# ard-dht.net
KiCad netlist of a schematic drawn in EAGLE
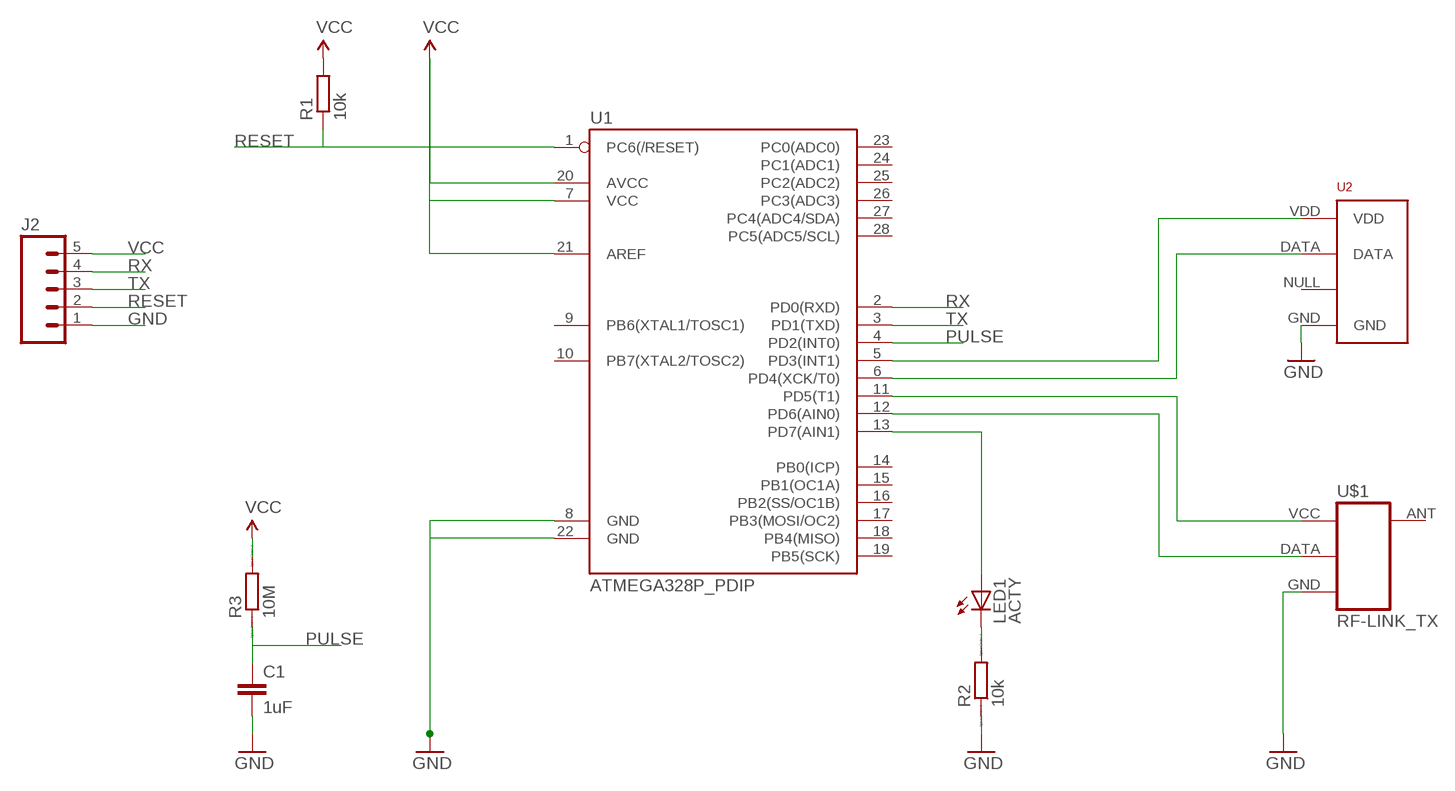
[diagram p0: schematic, sheet 1]

(export (version "E")
  (design (tool "Eeschema 10.0.6"))
  (components
    (comp (ref "C1")
      (value "1uF")
      (footprint "eagle-import:C5B5")
      (libsource (lib "eagle-import") (part "C5/5"))
    )
    (comp (ref "J2")
      (value "M05PTH_LONGPADS")
      (footprint "eagle-import:1X05_LONGPADS")
      (libsource (lib "eagle-import") (part "M05PTH_LONGPADS"))
    )
    (comp (ref "LED1")
      (value "ACTY")
      (footprint "eagle-import:LED3MM")
      (libsource (lib "eagle-import") (part "LED3MM"))
    )
    (comp (ref "R1")
      (value "10k")
      (footprint "eagle-import:0207_10")
      (libsource (lib "eagle-import") (part "R-EU_0207/10"))
    )
    (comp (ref "R2")
      (value "10k")
      (footprint "eagle-import:0204_7")
      (libsource (lib "eagle-import") (part "R0204/7"))
    )
    (comp (ref "R3")
      (value "10M")
      (footprint "eagle-import:0204_7")
      (libsource (lib "eagle-import") (part "R0204/7"))
    )
    (comp (ref "U$1")
      (value "RF-LINK_TX")
      (footprint "eagle-import:RF-LINK_TX")
      (libsource (lib "eagle-import") (part "RF-LINK_TX"))
    )
    (comp (ref "U1")
      (value "ATMEGA328P_PDIP")
      (footprint "eagle-import:DIL28-3")
      (libsource (lib "eagle-import") (part "ATMEGA328P_PDIP"))
    )
    (comp (ref "U2")
      (value "RHT03_DHT-22_AM2302")
      (footprint "eagle-import:RHT03_DHT-22")
      (libsource (lib "eagle-import") (part "RHT03_DHT-22_AM2302"))
    )
  )
  (nets
    (net (code "1") (name "/PULSE") (class "Default")
      (node (ref "C1") (pin "1") (pinfunction "1_1") (pintype "passive"))
      (node (ref "R3") (pin "1") (pinfunction "1_1") (pintype "passive"))
      (node (ref "U1") (pin "4") (pinfunction "PD2(INT0)_4") (pintype "bidirectional"))
    )
    (net (code "2") (name "/RESET") (class "Default")
      (node (ref "J2") (pin "2") (pinfunction "2_2") (pintype "passive"))
      (node (ref "R1") (pin "1") (pinfunction "1_1") (pintype "passive"))
      (node (ref "U1") (pin "1") (pinfunction "PC6(/RESET)_1") (pintype "bidirectional"))
    )
    (net (code "3") (name "/RX") (class "Default")
      (node (ref "J2") (pin "4") (pinfunction "4_4") (pintype "passive"))
      (node (ref "U1") (pin "2") (pinfunction "PD0(RXD)_2") (pintype "bidirectional"))
    )
    (net (code "4") (name "/TX") (class "Default")
      (node (ref "J2") (pin "3") (pinfunction "3_3") (pintype "passive"))
      (node (ref "U1") (pin "3") (pinfunction "PD1(TXD)_3") (pintype "bidirectional"))
    )
    (net (code "5") (name "GND") (class "Default")
      (node (ref "C1") (pin "2") (pinfunction "2_2") (pintype "passive"))
      (node (ref "J2") (pin "1") (pinfunction "1_1") (pintype "passive"))
      (node (ref "R2") (pin "1") (pinfunction "1_1") (pintype "passive"))
      (node (ref "U$1") (pin "GND") (pinfunction "GND_GND") (pintype "power_in"))
      (node (ref "U1") (pin "22") (pinfunction "GND_22") (pintype "bidirectional"))
      (node (ref "U1") (pin "8") (pinfunction "GND_8") (pintype "bidirectional"))
      (node (ref "U2") (pin "GND") (pinfunction "GND_GND") (pintype "power_in"))
    )
    (net (code "6") (name "Net-(LED1-C)") (class "Default")
      (node (ref "LED1") (pin "K") (pinfunction "C_K") (pintype "passive"))
      (node (ref "R2") (pin "2") (pinfunction "2_2") (pintype "passive"))
    )
    (net (code "7") (name "Net-(U$1-+5V)") (class "Default")
      (node (ref "U$1") (pin "VCC") (pinfunction "+5V_VCC") (pintype "power_in"))
      (node (ref "U1") (pin "11") (pinfunction "PD5(T1)_11") (pintype "bidirectional"))
    )
    (net (code "8") (name "Net-(U1-PD3(INT1))") (class "Default")
      (node (ref "U1") (pin "5") (pinfunction "PD3(INT1)_5") (pintype "bidirectional"))
      (node (ref "U2") (pin "VDD") (pinfunction "VDD_VDD") (pintype "power_in"))
    )
    (net (code "9") (name "Net-(U1-PD4(XCK{slash}T0))") (class "Default")
      (node (ref "U1") (pin "6") (pinfunction "PD4(XCK/T0)_6") (pintype "bidirectional"))
      (node (ref "U2") (pin "DATA") (pinfunction "DATA_DATA") (pintype "bidirectional"))
    )
    (net (code "10") (name "Net-(U1-PD6(AIN0))") (class "Default")
      (node (ref "U$1") (pin "DATA") (pinfunction "DATA_DATA") (pintype "input"))
      (node (ref "U1") (pin "12") (pinfunction "PD6(AIN0)_12") (pintype "bidirectional"))
    )
    (net (code "11") (name "Net-(U1-PD7(AIN1))") (class "Default")
      (node (ref "LED1") (pin "A") (pinfunction "A_A") (pintype "passive"))
      (node (ref "U1") (pin "13") (pinfunction "PD7(AIN1)_13") (pintype "bidirectional"))
    )
    (net (code "12") (name "VCC") (class "Default")
      (node (ref "J2") (pin "5") (pinfunction "5_5") (pintype "passive"))
      (node (ref "R1") (pin "2") (pinfunction "2_2") (pintype "passive"))
      (node (ref "R3") (pin "2") (pinfunction "2_2") (pintype "passive"))
      (node (ref "U1") (pin "20") (pinfunction "AVCC_20") (pintype "bidirectional"))
      (node (ref "U1") (pin "21") (pinfunction "AREF_21") (pintype "bidirectional"))
      (node (ref "U1") (pin "7") (pinfunction "VCC_7") (pintype "bidirectional"))
    )
    (net (code "13") (name "unconnected-(U$1-PadANT)") (class "Default")
      (node (ref "U$1") (pin "ANT") (pinfunction "ANT_ANT") (pintype "passive"))
    )
    (net (code "14") (name "unconnected-(U1-PB0(ICP)-Pad14)") (class "Default")
      (node (ref "U1") (pin "14") (pinfunction "PB0(ICP)_14") (pintype "bidirectional"))
    )
    (net (code "15") (name "unconnected-(U1-PB1(OC1A)-Pad15)") (class "Default")
      (node (ref "U1") (pin "15") (pinfunction "PB1(OC1A)_15") (pintype "bidirectional"))
    )
    (net (code "16") (name "unconnected-(U1-PB2(SS{slash}OC1B)-Pad16)") (class "Default")
      (node (ref "U1") (pin "16") (pinfunction "PB2(SS/OC1B)_16") (pintype "bidirectional"))
    )
    (net (code "17") (name "unconnected-(U1-PB3(MOSI{slash}OC2)-Pad17)") (class "Default")
      (node (ref "U1") (pin "17") (pinfunction "PB3(MOSI/OC2)_17") (pintype "bidirectional"))
    )
    (net (code "18") (name "unconnected-(U1-PB4(MISO)-Pad18)") (class "Default")
      (node (ref "U1") (pin "18") (pinfunction "PB4(MISO)_18") (pintype "bidirectional"))
    )
    (net (code "19") (name "unconnected-(U1-PB5(SCK)-Pad19)") (class "Default")
      (node (ref "U1") (pin "19") (pinfunction "PB5(SCK)_19") (pintype "bidirectional"))
    )
    (net (code "20") (name "unconnected-(U1-PB6(XTAL1{slash}TOSC1)-Pad9)") (class "Default")
      (node (ref "U1") (pin "9") (pinfunction "PB6(XTAL1/TOSC1)_9") (pintype "bidirectional"))
    )
    (net (code "21") (name "unconnected-(U1-PB7(XTAL2{slash}TOSC2)-Pad10)") (class "Default")
      (node (ref "U1") (pin "10") (pinfunction "PB7(XTAL2/TOSC2)_10") (pintype "bidirectional"))
    )
    (net (code "22") (name "unconnected-(U1-PC0(ADC0)-Pad23)") (class "Default")
      (node (ref "U1") (pin "23") (pinfunction "PC0(ADC0)_23") (pintype "bidirectional"))
    )
    (net (code "23") (name "unconnected-(U1-PC1(ADC1)-Pad24)") (class "Default")
      (node (ref "U1") (pin "24") (pinfunction "PC1(ADC1)_24") (pintype "bidirectional"))
    )
    (net (code "24") (name "unconnected-(U1-PC2(ADC2)-Pad25)") (class "Default")
      (node (ref "U1") (pin "25") (pinfunction "PC2(ADC2)_25") (pintype "bidirectional"))
    )
    (net (code "25") (name "unconnected-(U1-PC3(ADC3)-Pad26)") (class "Default")
      (node (ref "U1") (pin "26") (pinfunction "PC3(ADC3)_26") (pintype "bidirectional"))
    )
    (net (code "26") (name "unconnected-(U1-PC4(ADC4{slash}SDA)-Pad27)") (class "Default")
      (node (ref "U1") (pin "27") (pinfunction "PC4(ADC4/SDA)_27") (pintype "bidirectional"))
    )
    (net (code "27") (name "unconnected-(U1-PC5(ADC5{slash}SCL)-Pad28)") (class "Default")
      (node (ref "U1") (pin "28") (pinfunction "PC5(ADC5/SCL)_28") (pintype "bidirectional"))
    )
    (net (code "28") (name "unconnected-(U2-PadNULL)") (class "Default")
      (node (ref "U2") (pin "NULL") (pinfunction "NULL_NULL") (pintype "no_connect"))
    )
  )
)
